# LASER.net
KiCad netlist of a schematic drawn in Altium Designer
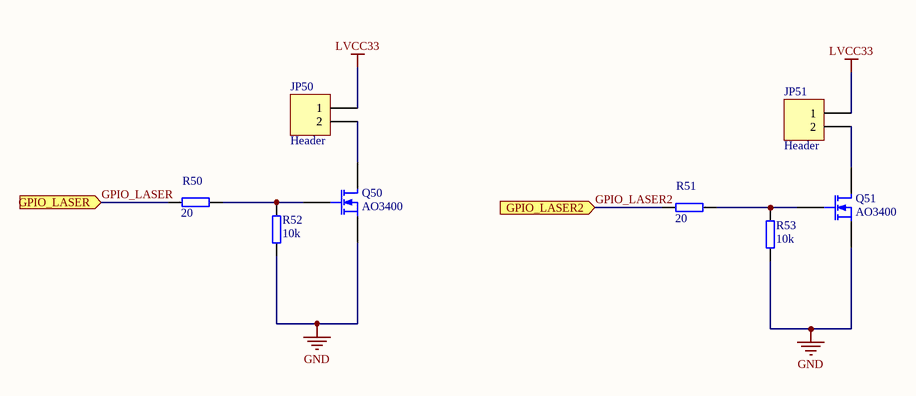
[diagram p0: LASER.SchDoc]

(export (version "E")
  (design (tool "Eeschema 10.0.6"))
  (components
    (comp (ref "JP50")
      (value "Header")
      (footprint "LASERJACK")
      (description "Header, 2-Pin")
      (libsource (lib "Miscellaneous Connectors") (part "Header 2"))
    )
    (comp (ref "JP51")
      (value "Header")
      (footprint "LASERJACK")
      (description "Header, 2-Pin")
      (libsource (lib "Miscellaneous Connectors") (part "Header 2"))
    )
    (comp (ref "Q50")
      (value "AO3400")
      (footprint "SI2300")
      (description "N-Channel MOSFET")
      (libsource (lib "Miscellaneous Devices") (part "MOSFET-N"))
    )
    (comp (ref "Q51")
      (value "AO3400")
      (footprint "SI2300")
      (description "N-Channel MOSFET")
      (libsource (lib "Miscellaneous Devices") (part "MOSFET-N"))
    )
    (comp (ref "R50") (value "20") (footprint "R0402") (libsource (lib "CxyDXP_SCH") (part "RES1")))
    (comp (ref "R51") (value "20") (footprint "R0402") (libsource (lib "CxyDXP_SCH") (part "RES1")))
    (comp (ref "R52") (value "10k") (footprint "R0402") (libsource (lib "CxyDXP_SCH") (part "RES1")))
    (comp (ref "R53") (value "10k") (footprint "R0402") (libsource (lib "CxyDXP_SCH") (part "RES1")))
  )
  (nets
    (net (code "1") (name "/GPIO_LASER") (class "Default")
      (node (ref "R50") (pin "2") (pinfunction "2_2") (pintype "passive"))
    )
    (net (code "2") (name "/GPIO_LASER2") (class "Default")
      (node (ref "R51") (pin "2") (pinfunction "2_2") (pintype "passive"))
    )
    (net (code "3") (name "GND") (class "Default")
      (node (ref "Q50") (pin "3") (pinfunction "S_3") (pintype "passive"))
      (node (ref "Q51") (pin "3") (pinfunction "S_3") (pintype "passive"))
      (node (ref "R52") (pin "2") (pinfunction "2_2") (pintype "passive"))
      (node (ref "R53") (pin "2") (pinfunction "2_2") (pintype "passive"))
    )
    (net (code "4") (name "LVCC33") (class "Default")
      (node (ref "JP50") (pin "1") (pinfunction "1_1") (pintype "passive"))
      (node (ref "JP51") (pin "1") (pinfunction "1_1") (pintype "passive"))
    )
    (net (code "5") (name "Net-(Q50-D)") (class "Default")
      (node (ref "JP50") (pin "2") (pinfunction "2_2") (pintype "passive"))
      (node (ref "Q50") (pin "1") (pinfunction "D_1") (pintype "passive"))
    )
    (net (code "6") (name "Net-(Q50-G)") (class "Default")
      (node (ref "Q50") (pin "2") (pinfunction "G_2") (pintype "passive"))
      (node (ref "R50") (pin "1") (pinfunction "1_1") (pintype "passive"))
      (node (ref "R52") (pin "1") (pinfunction "1_1") (pintype "passive"))
    )
    (net (code "7") (name "Net-(Q51-D)") (class "Default")
      (node (ref "JP51") (pin "2") (pinfunction "2_2") (pintype "passive"))
      (node (ref "Q51") (pin "1") (pinfunction "D_1") (pintype "passive"))
    )
    (net (code "8") (name "Net-(Q51-G)") (class "Default")
      (node (ref "Q51") (pin "2") (pinfunction "G_2") (pintype "passive"))
      (node (ref "R51") (pin "1") (pinfunction "1_1") (pintype "passive"))
      (node (ref "R53") (pin "1") (pinfunction "1_1") (pintype "passive"))
    )
  )
)
